# zigbee.net
KiCad netlist of a schematic drawn in Altium Designer
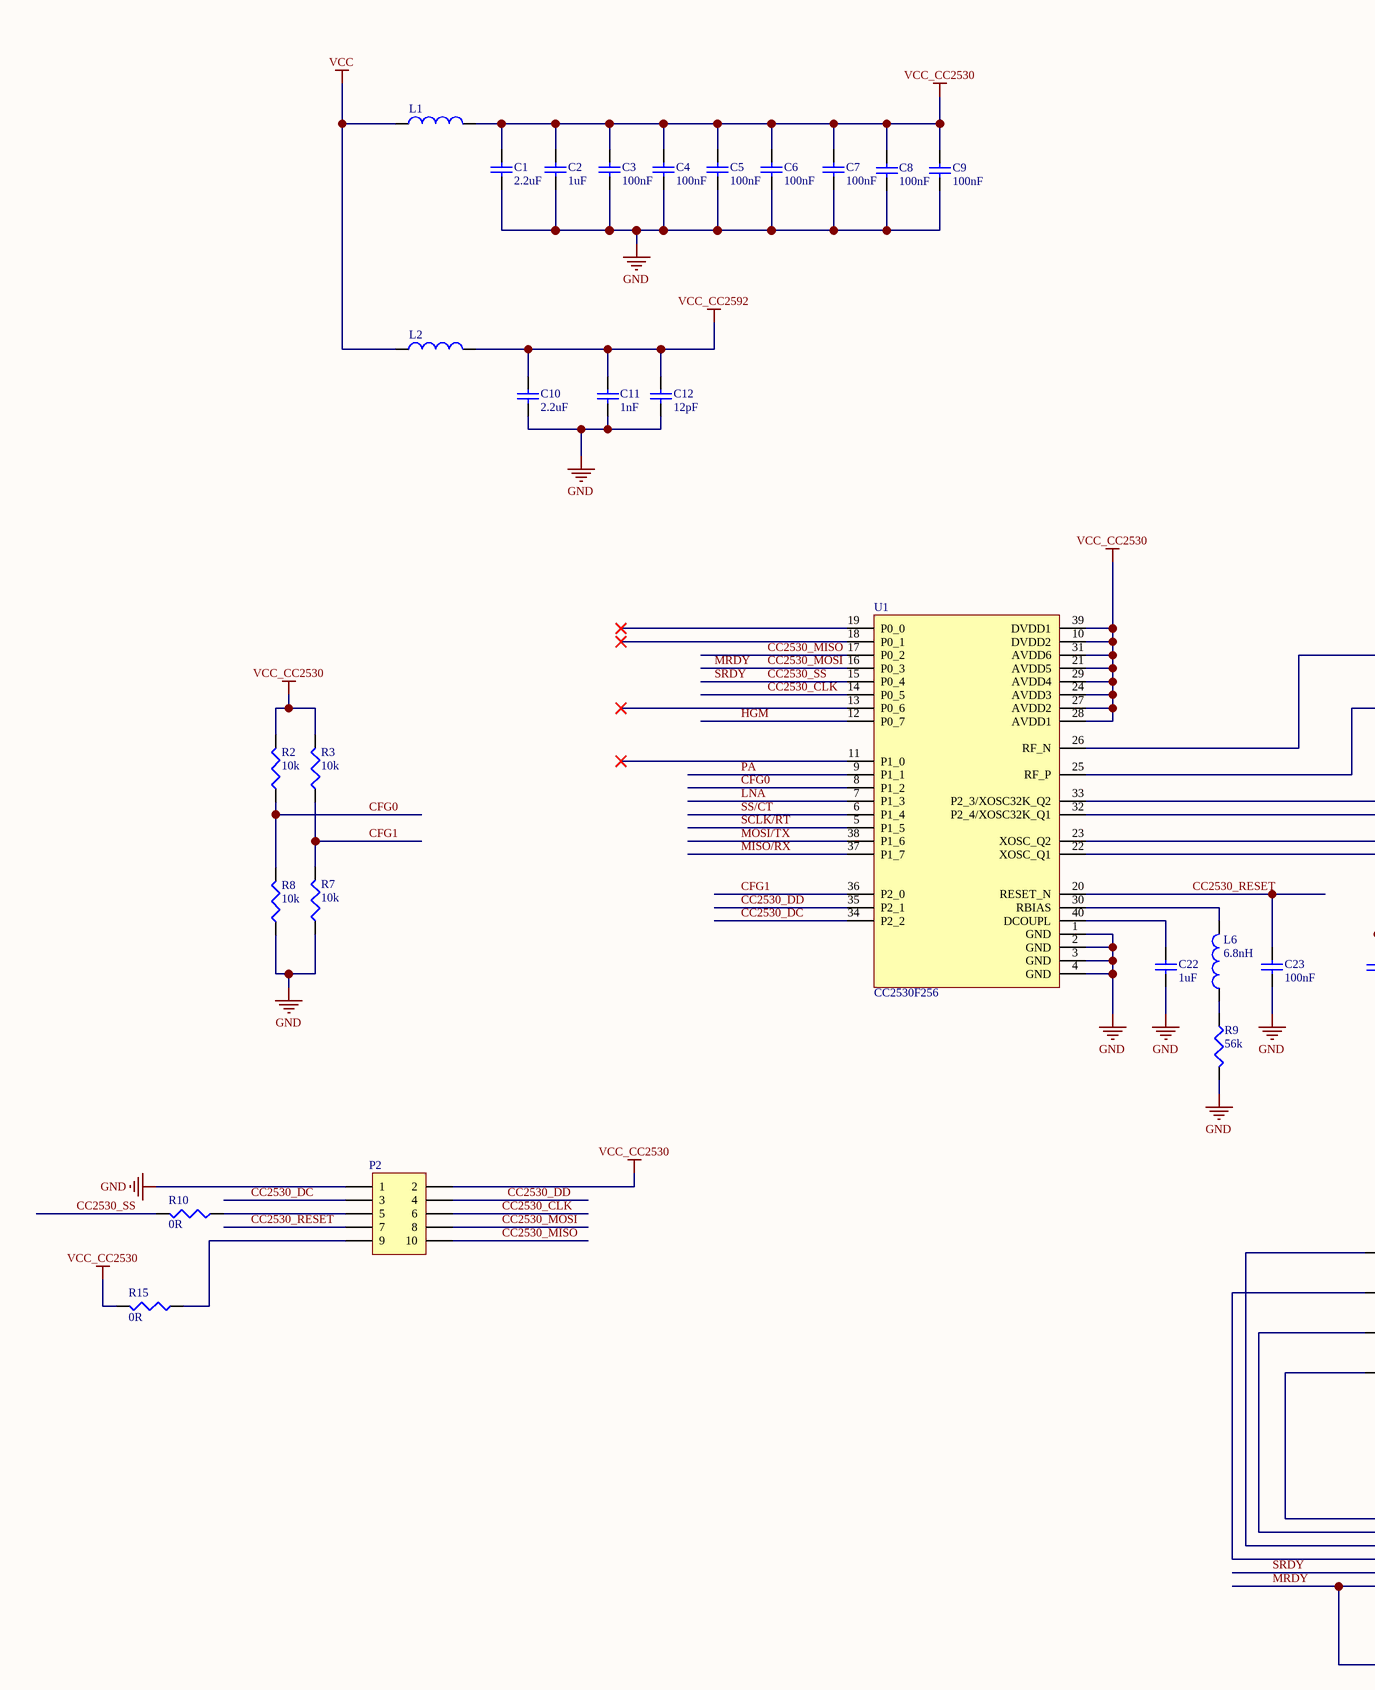
[diagram p0: zigbee.SchDoc, left]
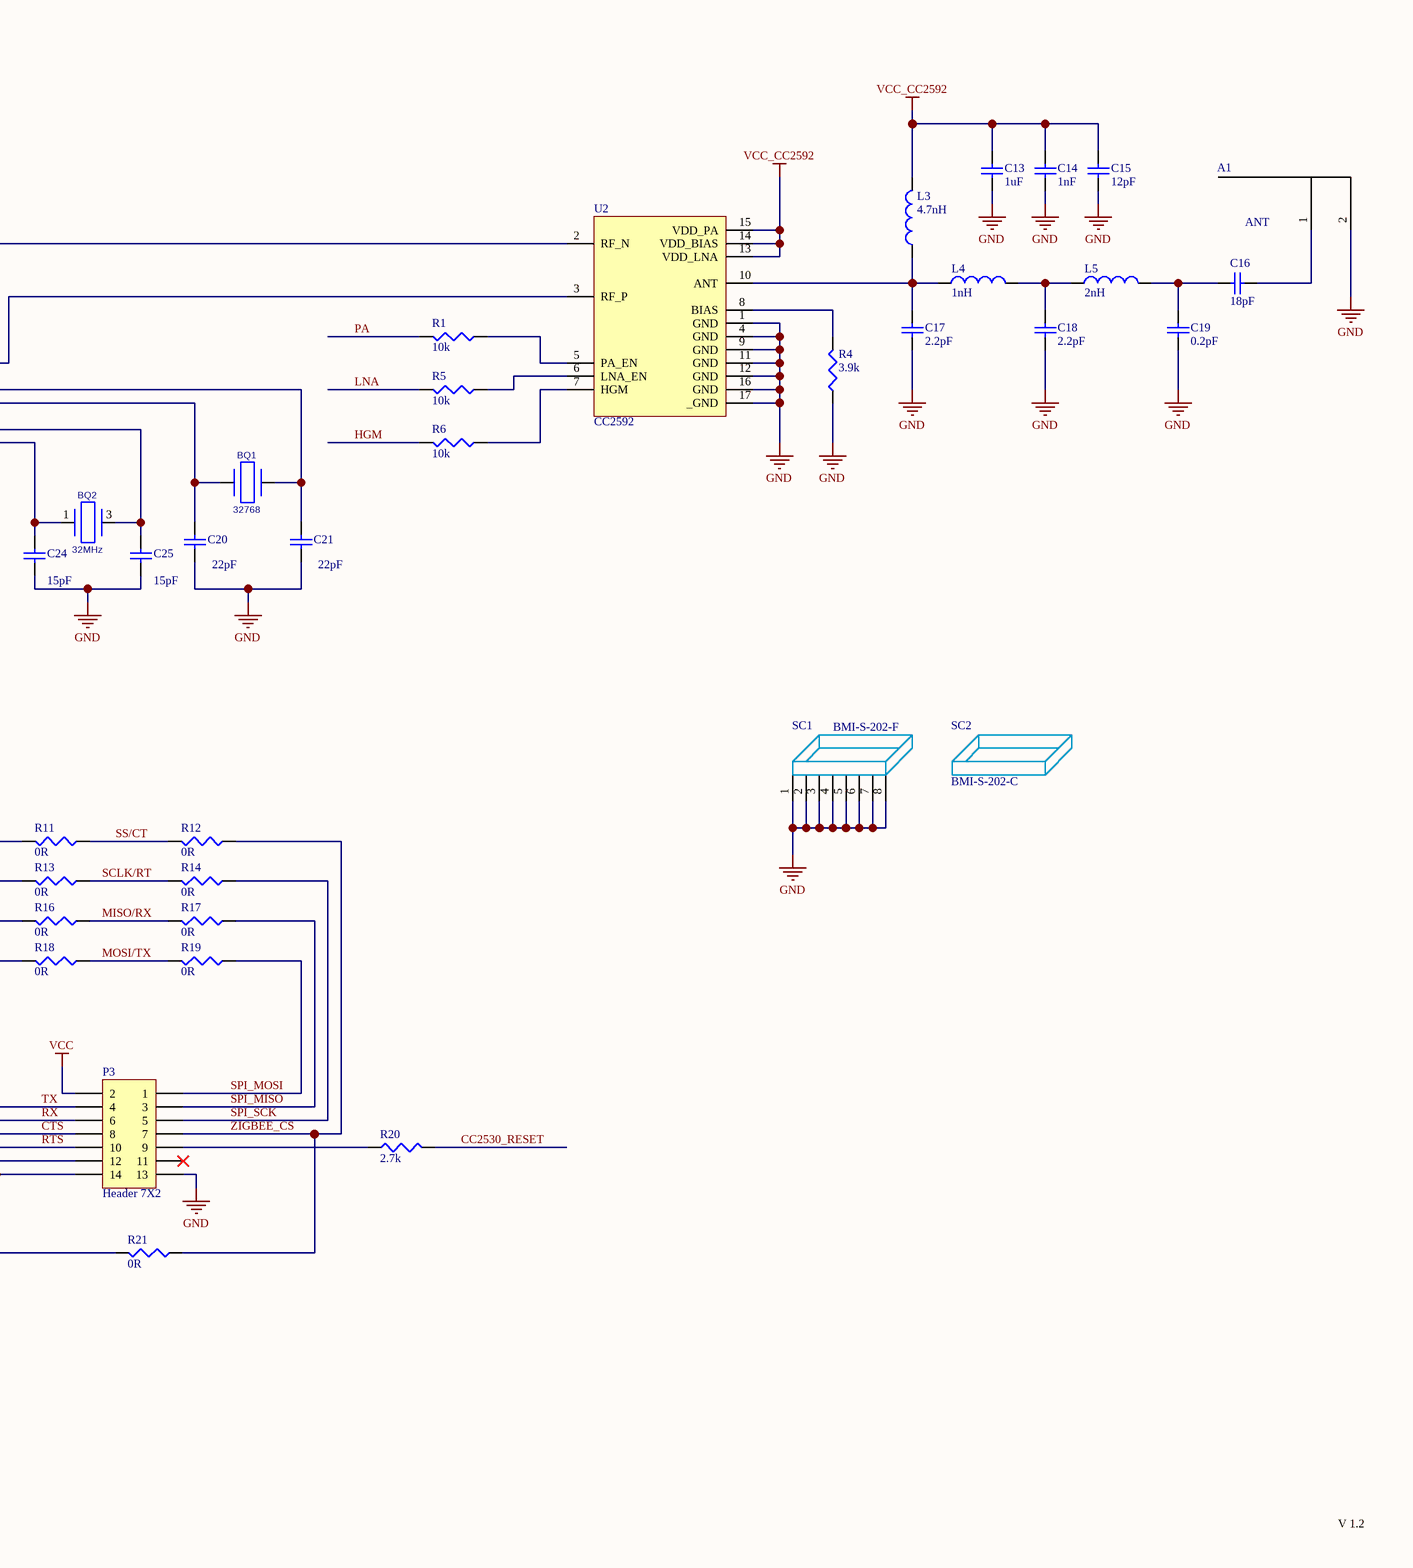
[diagram p1: zigbee.SchDoc, right]

(export (version "E")
  (design (tool "Eeschema 10.0.6"))
  (components
    (comp (ref "A1")
      (value "ANT")
      (footprint "F ant")
      (description "Inverted-F Antenna")
      (fields (field (name "MANUFACTURER PART NUMBER") "PCB ANT"))
      (libsource (lib "CC25xx") (part "ANT"))
    )
    (comp (ref "BQ1")
      (value "32768")
      (footprint "FC-12M")
      (description "CRYSTAL 32.768KHZ 12.5PF SMD")
      (fields
        (field (name "MANUFACTURER PART NUMBER") "FC-12M 32.7680KA-A3")
        (field (name "MANUFACTURER") "EPSON")
      )
      (libsource (lib "*") (part "6LC{colon}308C"))
    )
    (comp (ref "BQ2")
      (value "32MHz")
      (footprint "403C11A32M00000")
      (description "CRYSTAL 32MHZ 10PF SMD")
      (fields
        (field (name "MANUFACTURER PART NUMBER") "403C11A32M00000")
        (field (name "MANUFACTURER") "CTS-Frequency Controls")
      )
      (libsource (lib "*") (part "HC-49SMD"))
    )
    (comp (ref "C1")
      (value "2.2uF")
      (footprint "0402")
      (description "CAP CER 2.2UF 6.3V 20% X5R 0402")
      (fields
        (field (name "MANUFACTURER PART NUMBER") "CL05A225MQ5NNNC")
        (field (name "MANUFACTURER") "Samsung Electro-Mechanics America, Inc")
      )
      (libsource (lib "Miscellaneous Devices") (part "Cap"))
    )
    (comp (ref "C2")
      (value "1uF")
      (footprint "0402")
      (description "CAP CER 1UF 6.3V 10% X5R 0402")
      (fields
        (field (name "MANUFACTURER PART NUMBER") "GRM155R60J105KE19D")
        (field (name "MANUFACTURER") "Murata Electronics North America")
      )
      (libsource (lib "Miscellaneous Devices") (part "Cap"))
    )
    (comp (ref "C3")
      (value "100nF")
      (footprint "0402")
      (description "CAP CER 0.1UF 10V 20% X5R 0402")
      (fields
        (field (name "MANUFACTURER PART NUMBER") "CL05A104MP5NNNC")
        (field (name "MANUFACTURER") "Samsung Electro-Mechanics America, Inc")
      )
      (libsource (lib "Miscellaneous Devices") (part "Cap"))
    )
    (comp (ref "C4")
      (value "100nF")
      (footprint "0402")
      (description "CAP CER 0.1UF 10V 20% X5R 0402")
      (fields
        (field (name "MANUFACTURER PART NUMBER") "CL05A104MP5NNNC")
        (field (name "MANUFACTURER") "Samsung Electro-Mechanics America, Inc")
      )
      (libsource (lib "Miscellaneous Devices") (part "Cap"))
    )
    (comp (ref "C5")
      (value "100nF")
      (footprint "0402")
      (description "CAP CER 0.1UF 10V 20% X5R 0402")
      (fields
        (field (name "MANUFACTURER PART NUMBER") "CL05A104MP5NNNC")
        (field (name "MANUFACTURER") "Samsung Electro-Mechanics America, Inc")
      )
      (libsource (lib "Miscellaneous Devices") (part "Cap"))
    )
    (comp (ref "C6")
      (value "100nF")
      (footprint "0402")
      (description "CAP CER 0.1UF 10V 20% X5R 0402")
      (fields
        (field (name "MANUFACTURER PART NUMBER") "CL05A104MP5NNNC")
        (field (name "MANUFACTURER") "Samsung Electro-Mechanics America, Inc")
      )
      (libsource (lib "Miscellaneous Devices") (part "Cap"))
    )
    (comp (ref "C7")
      (value "100nF")
      (footprint "0402")
      (description "CAP CER 0.1UF 10V 20% X5R 0402")
      (fields
        (field (name "MANUFACTURER PART NUMBER") "CL05A104MP5NNNC")
        (field (name "MANUFACTURER") "Samsung Electro-Mechanics America, Inc")
      )
      (libsource (lib "Miscellaneous Devices") (part "Cap"))
    )
    (comp (ref "C8")
      (value "100nF")
      (footprint "0402")
      (description "CAP CER 0.1UF 10V 20% X5R 0402")
      (fields
        (field (name "MANUFACTURER PART NUMBER") "CL05A104MP5NNNC")
        (field (name "MANUFACTURER") "Samsung Electro-Mechanics America, Inc")
      )
      (libsource (lib "Miscellaneous Devices") (part "Cap"))
    )
    (comp (ref "C9")
      (value "100nF")
      (footprint "0402")
      (description "CAP CER 0.1UF 10V 20% X5R 0402")
      (fields
        (field (name "MANUFACTURER PART NUMBER") "CL05A104MP5NNNC")
        (field (name "MANUFACTURER") "Samsung Electro-Mechanics America, Inc")
      )
      (libsource (lib "Miscellaneous Devices") (part "Cap"))
    )
    (comp (ref "C10")
      (value "2.2uF")
      (footprint "0402")
      (description "CAP CER 2.2UF 6.3V 20% X5R 0402")
      (fields
        (field (name "MANUFACTURER PART NUMBER") "CL05A225MQ5NNNC")
        (field (name "MANUFACTURER") "Samsung Electro-Mechanics America, Inc")
      )
      (libsource (lib "Miscellaneous Devices") (part "Cap"))
    )
    (comp (ref "C11")
      (value "1nF")
      (footprint "0402")
      (description "CAP CER 10000PF 10V 10% X5R 0402")
      (fields
        (field (name "MANUFACTURER PART NUMBER") "GRM155R61A103KA01D")
        (field (name "MANUFACTURER") "Murata Electronics North America")
      )
      (libsource (lib "Miscellaneous Devices") (part "Cap"))
    )
    (comp (ref "C12")
      (value "12pF")
      (footprint "0402")
      (description "CAP CER 12PF 50V 5% NP0 0402")
      (fields
        (field (name "MANUFACTURER PART NUMBER") "GRM1555C1H120JA01D")
        (field (name "MANUFACTURER") "Murata Electronics North America")
      )
      (libsource (lib "Miscellaneous Devices") (part "Cap"))
    )
    (comp (ref "C13")
      (value "1uF")
      (footprint "0402")
      (description "CAP CER 1UF 6.3V 10% X5R 0402")
      (fields
        (field (name "MANUFACTURER PART NUMBER") "GRM155R60J105KE19D")
        (field (name "MANUFACTURER") "Murata Electronics North America")
      )
      (libsource (lib "Miscellaneous Devices") (part "Cap"))
    )
    (comp (ref "C14")
      (value "1nF")
      (footprint "0402")
      (description "CAP CER 10000PF 10V 10% X5R 0402")
      (fields
        (field (name "MANUFACTURER PART NUMBER") "GRM155R61A103KA01D")
        (field (name "MANUFACTURER") "Murata Electronics North America")
      )
      (libsource (lib "Miscellaneous Devices") (part "Cap"))
    )
    (comp (ref "C15")
      (value "12pF")
      (footprint "0402")
      (description "CAP CER 12PF 50V 5% NP0 0402")
      (fields
        (field (name "MANUFACTURER PART NUMBER") "GRM1555C1H120JA01D")
        (field (name "MANUFACTURER") "Murata Electronics North America")
      )
      (libsource (lib "Miscellaneous Devices") (part "Cap"))
    )
    (comp (ref "C16")
      (value "18pF")
      (footprint "0402")
      (description "CAP CER 18PF 50V 5% NP0 0402")
      (fields
        (field (name "MANUFACTURER PART NUMBER") "GRM1555C1H180JA01D")
        (field (name "MANUFACTURER") "Murata Electronics North America")
      )
      (libsource (lib "Miscellaneous Devices") (part "Cap"))
    )
    (comp (ref "C17")
      (value "2.2pF")
      (footprint "0402")
      (description "CAP CER 2.2PF 50V NP0 0402")
      (fields
        (field (name "MANUFACTURER PART NUMBER") "GRM1555C1H2R2BA01D")
        (field (name "MANUFACTURER") "Murata Electronics North America")
      )
      (libsource (lib "Miscellaneous Devices") (part "Cap"))
    )
    (comp (ref "C18")
      (value "2.2pF")
      (footprint "0402")
      (description "CAP CER 2.2PF 50V NP0 0402")
      (fields
        (field (name "MANUFACTURER PART NUMBER") "GRM1555C1H2R2BA01D")
        (field (name "MANUFACTURER") "Murata Electronics North America")
      )
      (libsource (lib "Miscellaneous Devices") (part "Cap"))
    )
    (comp (ref "C19")
      (value "0.2pF")
      (footprint "0402")
      (description "CAP CER 0.2PF 50V NP0 0402")
      (fields
        (field (name "MANUFACTURER PART NUMBER") "GJM1555C1HR20BB01D")
        (field (name "MANUFACTURER") "Murata Electronics North America")
      )
      (libsource (lib "Miscellaneous Devices") (part "Cap"))
    )
    (comp (ref "C20")
      (value "22pF")
      (footprint "0402")
      (description "CAP CER 22PF 50V 5% NP0 0402")
      (fields
        (field (name "MANUFACTURER PART NUMBER") "GRM1555C1H220JA01D")
        (field (name "MANUFACTURER") "Murata Electronics North America")
      )
      (libsource (lib "Miscellaneous Devices") (part "Cap"))
    )
    (comp (ref "C21")
      (value "22pF")
      (footprint "0402")
      (description "CAP CER 22PF 50V 5% NP0 0402")
      (fields
        (field (name "MANUFACTURER PART NUMBER") "GRM1555C1H220JA01D")
        (field (name "MANUFACTURER") "Murata Electronics North America")
      )
      (libsource (lib "Miscellaneous Devices") (part "Cap"))
    )
    (comp (ref "C22")
      (value "1uF")
      (footprint "0402")
      (description "CAP CER 1UF 6.3V 10% X5R 0402")
      (fields
        (field (name "MANUFACTURER PART NUMBER") "GRM155R60J105KE19D")
        (field (name "MANUFACTURER") "Murata Electronics North America")
      )
      (libsource (lib "Miscellaneous Devices") (part "Cap"))
    )
    (comp (ref "C23")
      (value "100nF")
      (footprint "0402")
      (description "CAP CER 0.1UF 10V 20% X5R 0402")
      (fields
        (field (name "MANUFACTURER PART NUMBER") "CL05A104MP5NNNC")
        (field (name "MANUFACTURER") "Samsung Electro-Mechanics America, Inc")
      )
      (libsource (lib "Miscellaneous Devices") (part "Cap"))
    )
    (comp (ref "C24")
      (value "15pF")
      (footprint "0402")
      (description "CAP CER 15PF 50V 5% NP0 0402")
      (fields
        (field (name "MANUFACTURER PART NUMBER") "GRM1555C1H150JA01D")
        (field (name "MANUFACTURER") "Murata Electronics North America")
      )
      (libsource (lib "Miscellaneous Devices") (part "Cap"))
    )
    (comp (ref "C25")
      (value "15pF")
      (footprint "0402")
      (description "CAP CER 15PF 50V 5% NP0 0402")
      (fields
        (field (name "MANUFACTURER PART NUMBER") "GRM1555C1H150JA01D")
        (field (name "MANUFACTURER") "Murata Electronics North America")
      )
      (libsource (lib "Miscellaneous Devices") (part "Cap"))
    )
    (comp (ref "L1")
      (value "Inductor")
      (footprint "0402")
      (description "FILTER CHIP 1000 OHM 250MA 0402")
      (fields
        (field (name "MANUFACTURER PART NUMBER") "BLM15HG102SN1D")
        (field (name "MANUFACTURER") "Murata Electronics North America")
      )
      (libsource (lib "Miscellaneous Devices") (part "Inductor"))
    )
    (comp (ref "L2")
      (value "Inductor")
      (footprint "0603")
      (description "FILTER CHIP 1000 OHM 250MA 0603")
      (fields
        (field (name "MANUFACTURER PART NUMBER") "BLM18HE152SN1D")
        (field (name "MANUFACTURER") "Murata Electronics North America")
      )
      (libsource (lib "Miscellaneous Devices") (part "Inductor"))
    )
    (comp (ref "L3")
      (value "4.7nH")
      (footprint "0402")
      (description "INDUCTOR 4.7NH 300MA 0402")
      (fields
        (field (name "MANUFACTURER PART NUMBER") "LQG15HN4N7S02D")
        (field (name "MANUFACTURER") "Murata Electronics North America")
      )
      (libsource (lib "Miscellaneous Devices") (part "Inductor"))
    )
    (comp (ref "L4")
      (value "1nH")
      (footprint "0402")
      (description "INDUCTOR 1.0NH 300MA 0402")
      (fields
        (field (name "MANUFACTURER PART NUMBER") "LQG15HN1N0S02D")
        (field (name "MANUFACTURER") "Murata Electronics North America")
      )
      (libsource (lib "Miscellaneous Devices") (part "Inductor"))
    )
    (comp (ref "L5")
      (value "2nH")
      (footprint "0402")
      (description "INDUCTOR 2.0NH 300MA 0402")
      (fields
        (field (name "MANUFACTURER PART NUMBER") "LQG15HS2N0S02D")
        (field (name "MANUFACTURER") "Murata Electronics North America")
      )
      (libsource (lib "Miscellaneous Devices") (part "Inductor"))
    )
    (comp (ref "L6")
      (value "6.8nH")
      (footprint "0402")
      (description "INDUCTOR 6.8NH 300MA 0402")
      (fields
        (field (name "MANUFACTURER PART NUMBER") "LQG15HS6N8J02D")
        (field (name "MANUFACTURER") "Murata Electronics North America")
      )
      (libsource (lib "Miscellaneous Devices") (part "Inductor"))
    )
    (comp (ref "P2")
      (value "*")
      (footprint "HDR2X5H")
      (description "CONN HEADER R/A DUAL 10POS GOLD")
      (fields (field (name "MANUFACTURER PART NUMBER") "961210-5604-AR") (field (name "MANUFACTURER") "3M"))
      (libsource (lib "Miscellaneous Connectors") (part "Header 5X2"))
    )
    (comp (ref "P3")
      (value "Header 7X2")
      (footprint "DIP14")
      (description "BERGSTIK II .100\" DR STRAIGHT")
      (fields (field (name "MANUFACTURER PART NUMBER") "67996-114HLF") (field (name "MANUFACTURER") "FCI"))
      (libsource (lib "Miscellaneous Connectors") (part "Header 7X2"))
    )
    (comp (ref "R1")
      (value "10k")
      (footprint "0402")
      (description "RES 10K OHM 1/10W 5% 0402 SMD")
      (fields
        (field (name "MANUFACTURER PART NUMBER") "ERJ-2GEJ103X")
        (field (name "MANUFACTURER") "Panasonic Electronic Components")
      )
      (libsource (lib "Miscellaneous Devices") (part "Res3"))
    )
    (comp (ref "R2")
      (value "10k")
      (footprint "0402")
      (description "RES 10K OHM 1/10W 5% 0402 SMD")
      (fields
        (field (name "MANUFACTURER PART NUMBER") "ERJ-2GEJ103X")
        (field (name "MANUFACTURER") "Panasonic Electronic Components")
      )
      (libsource (lib "Miscellaneous Devices") (part "Res3"))
    )
    (comp (ref "R3")
      (value "10k")
      (footprint "0402")
      (description "RES 10K OHM 1/10W 5% 0402 SMD")
      (fields
        (field (name "MANUFACTURER PART NUMBER") "ERJ-2GEJ103X")
        (field (name "MANUFACTURER") "Panasonic Electronic Components")
      )
      (libsource (lib "Miscellaneous Devices") (part "Res3"))
    )
    (comp (ref "R4")
      (value "3.9k")
      (footprint "0402")
      (description "RES 3.9K OHM 1/10W 1% 0402 SMD")
      (fields
        (field (name "MANUFACTURER PART NUMBER") "ERJ-2RKF3901X")
        (field (name "MANUFACTURER") "Panasonic Electronic Components")
      )
      (libsource (lib "Miscellaneous Devices") (part "Res3"))
    )
    (comp (ref "R5")
      (value "10k")
      (footprint "0402")
      (description "RES 10K OHM 1/10W 5% 0402 SMD")
      (fields
        (field (name "MANUFACTURER PART NUMBER") "ERJ-2GEJ103X")
        (field (name "MANUFACTURER") "Panasonic Electronic Components")
      )
      (libsource (lib "Miscellaneous Devices") (part "Res3"))
    )
    (comp (ref "R6")
      (value "10k")
      (footprint "0402")
      (description "RES 10K OHM 1/10W 5% 0402 SMD")
      (fields
        (field (name "MANUFACTURER PART NUMBER") "ERJ-2GEJ103X")
        (field (name "MANUFACTURER") "Panasonic Electronic Components")
      )
      (libsource (lib "Miscellaneous Devices") (part "Res3"))
    )
    (comp (ref "R7")
      (value "10k")
      (footprint "0402")
      (description "RES 10K OHM 1/10W 5% 0402 SMD")
      (fields
        (field (name "MANUFACTURER PART NUMBER") "ERJ-2GEJ103X")
        (field (name "MANUFACTURER") "Panasonic Electronic Components")
      )
      (libsource (lib "Miscellaneous Devices") (part "Res3"))
    )
    (comp (ref "R8")
      (value "10k")
      (footprint "0402")
      (description "RES 10K OHM 1/10W 5% 0402 SMD")
      (fields
        (field (name "MANUFACTURER PART NUMBER") "ERJ-2GEJ103X")
        (field (name "MANUFACTURER") "Panasonic Electronic Components")
      )
      (libsource (lib "Miscellaneous Devices") (part "Res3"))
    )
    (comp (ref "R9")
      (value "56k")
      (footprint "0402")
      (description "RES 56K OHM 1/10W 1% 0402 SMD")
      (fields
        (field (name "MANUFACTURER PART NUMBER") "ERJ-2RKF5602X")
        (field (name "MANUFACTURER") "Panasonic Electronic Components")
      )
      (libsource (lib "Miscellaneous Devices") (part "Res3"))
    )
    (comp (ref "R10")
      (value "0R")
      (footprint "0402")
      (description "RES 0.0 OHM 1/10W JUMP 0402 SMD")
      (fields
        (field (name "MANUFACTURER PART NUMBER") "ERJ-2GE0R00X")
        (field (name "MANUFACTURER") "Panasonic Electronic Components")
      )
      (libsource (lib "Miscellaneous Devices") (part "Res3"))
    )
    (comp (ref "R11")
      (value "0R")
      (footprint "0402")
      (description "RES 0.0 OHM 1/10W JUMP 0402 SMD")
      (fields
        (field (name "MANUFACTURER PART NUMBER") "ERJ-2GE0R00X")
        (field (name "MANUFACTURER") "Panasonic Electronic Components")
      )
      (libsource (lib "Miscellaneous Devices") (part "Res3"))
    )
    (comp (ref "R12")
      (value "0R")
      (footprint "0402")
      (description "RES 0.0 OHM 1/10W JUMP 0402 SMD")
      (fields
        (field (name "MANUFACTURER PART NUMBER") "ERJ-2GE0R00X")
        (field (name "MANUFACTURER") "Panasonic Electronic Components")
      )
      (libsource (lib "Miscellaneous Devices") (part "Res3"))
    )
    (comp (ref "R13")
      (value "0R")
      (footprint "0402")
      (description "RES 0.0 OHM 1/10W JUMP 0402 SMD")
      (fields
        (field (name "MANUFACTURER PART NUMBER") "ERJ-2GE0R00X")
        (field (name "MANUFACTURER") "Panasonic Electronic Components")
      )
      (libsource (lib "Miscellaneous Devices") (part "Res3"))
    )
    (comp (ref "R14")
      (value "0R")
      (footprint "0402")
      (description "RES 0.0 OHM 1/10W JUMP 0402 SMD")
      (fields
        (field (name "MANUFACTURER PART NUMBER") "ERJ-2GE0R00X")
        (field (name "MANUFACTURER") "Panasonic Electronic Components")
      )
      (libsource (lib "Miscellaneous Devices") (part "Res3"))
    )
    (comp (ref "R15")
      (value "0R")
      (footprint "0402")
      (description "RES 0.0 OHM 1/10W JUMP 0402 SMD")
      (fields
        (field (name "MANUFACTURER PART NUMBER") "ERJ-2GE0R00X")
        (field (name "MANUFACTURER") "Panasonic Electronic Components")
      )
      (libsource (lib "Miscellaneous Devices") (part "Res3"))
    )
    (comp (ref "R16")
      (value "0R")
      (footprint "0402")
      (description "RES 0.0 OHM 1/10W JUMP 0402 SMD")
      (fields
        (field (name "MANUFACTURER PART NUMBER") "ERJ-2GE0R00X")
        (field (name "MANUFACTURER") "Panasonic Electronic Components")
      )
      (libsource (lib "Miscellaneous Devices") (part "Res3"))
    )
    (comp (ref "R17")
      (value "0R")
      (footprint "0402")
      (description "RES 0.0 OHM 1/10W JUMP 0402 SMD")
      (fields
        (field (name "MANUFACTURER PART NUMBER") "ERJ-2GE0R00X")
        (field (name "MANUFACTURER") "Panasonic Electronic Components")
      )
      (libsource (lib "Miscellaneous Devices") (part "Res3"))
    )
    (comp (ref "R18")
      (value "0R")
      (footprint "0402")
      (description "RES 0.0 OHM 1/10W JUMP 0402 SMD")
      (fields
        (field (name "MANUFACTURER PART NUMBER") "ERJ-2GE0R00X")
        (field (name "MANUFACTURER") "Panasonic Electronic Components")
      )
      (libsource (lib "Miscellaneous Devices") (part "Res3"))
    )
    (comp (ref "R19")
      (value "0R")
      (footprint "0402")
      (description "RES 0.0 OHM 1/10W JUMP 0402 SMD")
      (fields
        (field (name "MANUFACTURER PART NUMBER") "ERJ-2GE0R00X")
        (field (name "MANUFACTURER") "Panasonic Electronic Components")
      )
      (libsource (lib "Miscellaneous Devices") (part "Res3"))
    )
    (comp (ref "R20")
      (value "2.7k")
      (footprint "0402")
      (description "RES 2.7K OHM 1/10W 5% 0402 SMD")
      (fields
        (field (name "MANUFACTURER PART NUMBER") "ERJ-2GEJ272X")
        (field (name "MANUFACTURER") "Panasonic Electronic Components")
      )
      (libsource (lib "Miscellaneous Devices") (part "Res3"))
    )
    (comp (ref "R21")
      (value "0R")
      (footprint "0402")
      (description "RES 0.0 OHM 1/10W JUMP 0402 SMD")
      (fields
        (field (name "MANUFACTURER PART NUMBER") "ERJ-2GE0R00X")
        (field (name "MANUFACTURER") "Panasonic Electronic Components")
      )
      (libsource (lib "Miscellaneous Devices") (part "Res3"))
    )
    (comp (ref "SC1")
      (value "BMI-S-202-F")
      (footprint "BMIS_202_F")
      (description "BOARD SHIELD .65X.65\" FRAME")
      (fields (field (name "MANUFACTURER") "Laird Technologies EMI"))
      (libsource (lib "CC25xx") (part "BMI-S-202-F"))
    )
    (comp (ref "SC2")
      (value "BMI-S-202-C")
      (description "BOARD SHIELD .65X.65\" COVER")
      (fields (field (name "MANUFACTURER") "Laird Technologies EMI"))
      (libsource (lib "CC25xx") (part "BMI-S-202-C"))
    )
    (comp (ref "U1")
      (value "CC2530F256")
      (footprint "QFN40")
      (description "IC SOC IEEE 802.15.4/ZIG 40VQFN")
      (fields
        (field (name "MANUFACTURER PART NUMBER") "CC2530F256RHAT")
        (field (name "MANUFACTURER") "Texas Instruments")
      )
      (libsource (lib "CC25xx") (part "CC2530F256"))
    )
    (comp (ref "U2")
      (value "CC2592")
      (footprint "QFN16")
      (description "IC RF FRONT END 2.4GHZ 16-VQFN")
      (fields
        (field (name "MANUFACTURER PART NUMBER") "CC2592RGVT")
        (field (name "MANUFACTURER") "Texas Instruments")
      )
      (libsource (lib "CC25xx") (part "CC2592"))
    )
  )
  (nets
    (net (code "1") (name "/CC2530_CLK") (class "Default")
      (node (ref "P2") (pin "6") (pinfunction "6_6") (pintype "passive"))
      (node (ref "U1") (pin "14") (pinfunction "P0_5_14") (pintype "passive"))
    )
    (net (code "2") (name "/CC2530_DC") (class "Default")
      (node (ref "P2") (pin "3") (pinfunction "3_3") (pintype "passive"))
      (node (ref "U1") (pin "34") (pinfunction "P2_2_34") (pintype "passive"))
    )
    (net (code "3") (name "/CC2530_DD") (class "Default")
      (node (ref "P2") (pin "4") (pinfunction "4_4") (pintype "passive"))
      (node (ref "U1") (pin "35") (pinfunction "P2_1_35") (pintype "passive"))
    )
    (net (code "4") (name "/CC2530_MISO") (class "Default")
      (node (ref "P2") (pin "10") (pinfunction "10_10") (pintype "passive"))
      (node (ref "U1") (pin "17") (pinfunction "P0_2_17") (pintype "passive"))
    )
    (net (code "5") (name "/CC2530_MOSI") (class "Default")
      (node (ref "P2") (pin "8") (pinfunction "8_8") (pintype "passive"))
      (node (ref "P3") (pin "14") (pinfunction "14_14") (pintype "passive"))
      (node (ref "R21") (pin "2") (pinfunction "2_2") (pintype "passive"))
      (node (ref "U1") (pin "16") (pinfunction "P0_3_16") (pintype "passive"))
    )
    (net (code "6") (name "/CC2530_RESET") (class "Default")
      (node (ref "C23") (pin "1") (pinfunction "1_1") (pintype "passive"))
      (node (ref "P2") (pin "7") (pinfunction "7_7") (pintype "passive"))
      (node (ref "R20") (pin "1") (pinfunction "1_1") (pintype "passive"))
      (node (ref "U1") (pin "20") (pinfunction "RESET_N_20") (pintype "passive"))
    )
    (net (code "7") (name "/CC2530_SS") (class "Default")
      (node (ref "P3") (pin "12") (pinfunction "12_12") (pintype "passive"))
      (node (ref "R10") (pin "2") (pinfunction "2_2") (pintype "passive"))
      (node (ref "U1") (pin "15") (pinfunction "P0_4_15") (pintype "passive"))
    )
    (net (code "8") (name "/CFG0") (class "Default")
      (node (ref "R2") (pin "2") (pinfunction "2_2") (pintype "passive"))
      (node (ref "R8") (pin "1") (pinfunction "1_1") (pintype "passive"))
      (node (ref "U1") (pin "8") (pinfunction "P1_2_8") (pintype "passive"))
    )
    (net (code "9") (name "/CFG1") (class "Default")
      (node (ref "R3") (pin "2") (pinfunction "2_2") (pintype "passive"))
      (node (ref "R7") (pin "1") (pinfunction "1_1") (pintype "passive"))
      (node (ref "U1") (pin "36") (pinfunction "P2_0_36") (pintype "passive"))
    )
    (net (code "10") (name "/CTS") (class "Default")
      (node (ref "P3") (pin "8") (pinfunction "8_8") (pintype "passive"))
      (node (ref "R11") (pin "2") (pinfunction "2_2") (pintype "passive"))
    )
    (net (code "11") (name "/HGM") (class "Default")
      (node (ref "R6") (pin "1") (pinfunction "1_1") (pintype "passive"))
      (node (ref "U1") (pin "12") (pinfunction "P0_7_12") (pintype "passive"))
    )
    (net (code "12") (name "/LNA") (class "Default")
      (node (ref "R5") (pin "1") (pinfunction "1_1") (pintype "passive"))
      (node (ref "U1") (pin "7") (pinfunction "P1_3_7") (pintype "passive"))
    )
    (net (code "13") (name "/MISO{slash}RX") (class "Default")
      (node (ref "R16") (pin "1") (pinfunction "1_1") (pintype "passive"))
      (node (ref "R17") (pin "2") (pinfunction "2_2") (pintype "passive"))
      (node (ref "U1") (pin "37") (pinfunction "P1_7_37") (pintype "passive"))
    )
    (net (code "14") (name "/MOSI{slash}TX") (class "Default")
      (node (ref "R18") (pin "1") (pinfunction "1_1") (pintype "passive"))
      (node (ref "R19") (pin "2") (pinfunction "2_2") (pintype "passive"))
      (node (ref "U1") (pin "38") (pinfunction "P1_6_38") (pintype "passive"))
    )
    (net (code "15") (name "/PA") (class "Default")
      (node (ref "R1") (pin "1") (pinfunction "1_1") (pintype "passive"))
      (node (ref "U1") (pin "9") (pinfunction "P1_1_9") (pintype "passive"))
    )
    (net (code "16") (name "/RTS") (class "Default")
      (node (ref "P3") (pin "10") (pinfunction "10_10") (pintype "passive"))
      (node (ref "R13") (pin "2") (pinfunction "2_2") (pintype "passive"))
    )
    (net (code "17") (name "/RX") (class "Default")
      (node (ref "P3") (pin "6") (pinfunction "6_6") (pintype "passive"))
      (node (ref "R16") (pin "2") (pinfunction "2_2") (pintype "passive"))
    )
    (net (code "18") (name "/SCLK{slash}RT") (class "Default")
      (node (ref "R13") (pin "1") (pinfunction "1_1") (pintype "passive"))
      (node (ref "R14") (pin "2") (pinfunction "2_2") (pintype "passive"))
      (node (ref "U1") (pin "5") (pinfunction "P1_5_5") (pintype "passive"))
    )
    (net (code "19") (name "/SPI_MISO") (class "Default")
      (node (ref "P3") (pin "3") (pinfunction "3_3") (pintype "passive"))
      (node (ref "R17") (pin "1") (pinfunction "1_1") (pintype "passive"))
    )
    (net (code "20") (name "/SPI_MOSI") (class "Default")
      (node (ref "P3") (pin "1") (pinfunction "1_1") (pintype "passive"))
      (node (ref "R19") (pin "1") (pinfunction "1_1") (pintype "passive"))
    )
    (net (code "21") (name "/SPI_SCK") (class "Default")
      (node (ref "P3") (pin "5") (pinfunction "5_5") (pintype "passive"))
      (node (ref "R14") (pin "1") (pinfunction "1_1") (pintype "passive"))
    )
    (net (code "22") (name "/SS{slash}CT") (class "Default")
      (node (ref "R11") (pin "1") (pinfunction "1_1") (pintype "passive"))
      (node (ref "R12") (pin "2") (pinfunction "2_2") (pintype "passive"))
      (node (ref "U1") (pin "6") (pinfunction "P1_4_6") (pintype "passive"))
    )
    (net (code "23") (name "/TX") (class "Default")
      (node (ref "P3") (pin "4") (pinfunction "4_4") (pintype "passive"))
      (node (ref "R18") (pin "2") (pinfunction "2_2") (pintype "passive"))
    )
    (net (code "24") (name "/ZIGBEE_CS") (class "Default")
      (node (ref "P3") (pin "7") (pinfunction "7_7") (pintype "passive"))
      (node (ref "R12") (pin "1") (pinfunction "1_1") (pintype "passive"))
      (node (ref "R21") (pin "1") (pinfunction "1_1") (pintype "passive"))
    )
    (net (code "25") (name "GND") (class "Default")
      (node (ref "A1") (pin "2") (pinfunction "2_2") (pintype "passive"))
      (node (ref "C1") (pin "2") (pinfunction "2_2") (pintype "passive"))
      (node (ref "C10") (pin "2") (pinfunction "2_2") (pintype "passive"))
      (node (ref "C11") (pin "1") (pinfunction "1_1") (pintype "passive"))
      (node (ref "C12") (pin "1") (pinfunction "1_1") (pintype "passive"))
      (node (ref "C13") (pin "1") (pinfunction "1_1") (pintype "passive"))
      (node (ref "C14") (pin "1") (pinfunction "1_1") (pintype "passive"))
      (node (ref "C15") (pin "1") (pinfunction "1_1") (pintype "passive"))
      (node (ref "C17") (pin "1") (pinfunction "1_1") (pintype "passive"))
      (node (ref "C18") (pin "1") (pinfunction "1_1") (pintype "passive"))
      (node (ref "C19") (pin "1") (pinfunction "1_1") (pintype "passive"))
      (node (ref "C2") (pin "2") (pinfunction "2_2") (pintype "passive"))
      (node (ref "C20") (pin "1") (pinfunction "1_1") (pintype "passive"))
      (node (ref "C21") (pin "1") (pinfunction "1_1") (pintype "passive"))
      (node (ref "C22") (pin "2") (pinfunction "2_2") (pintype "passive"))
      (node (ref "C23") (pin "2") (pinfunction "2_2") (pintype "passive"))
      (node (ref "C24") (pin "1") (pinfunction "1_1") (pintype "passive"))
      (node (ref "C25") (pin "1") (pinfunction "1_1") (pintype "passive"))
      (node (ref "C3") (pin "2") (pinfunction "2_2") (pintype "passive"))
      (node (ref "C4") (pin "2") (pinfunction "2_2") (pintype "passive"))
      (node (ref "C5") (pin "2") (pinfunction "2_2") (pintype "passive"))
      (node (ref "C6") (pin "2") (pinfunction "2_2") (pintype "passive"))
      (node (ref "C7") (pin "2") (pinfunction "2_2") (pintype "passive"))
      (node (ref "C8") (pin "2") (pinfunction "2_2") (pintype "passive"))
      (node (ref "C9") (pin "2") (pinfunction "2_2") (pintype "passive"))
      (node (ref "P2") (pin "1") (pinfunction "1_1") (pintype "passive"))
      (node (ref "P3") (pin "13") (pinfunction "13_13") (pintype "passive"))
      (node (ref "R4") (pin "1") (pinfunction "1_1") (pintype "passive"))
      (node (ref "R7") (pin "2") (pinfunction "2_2") (pintype "passive"))
      (node (ref "R8") (pin "2") (pinfunction "2_2") (pintype "passive"))
      (node (ref "R9") (pin "2") (pinfunction "2_2") (pintype "passive"))
      (node (ref "SC1") (pin "1") (pinfunction "1_1") (pintype "passive"))
      (node (ref "SC1") (pin "2") (pinfunction "2_2") (pintype "passive"))
      (node (ref "SC1") (pin "3") (pinfunction "3_3") (pintype "passive"))
      (node (ref "SC1") (pin "4") (pinfunction "4_4") (pintype "passive"))
      (node (ref "SC1") (pin "5") (pinfunction "5_5") (pintype "passive"))
      (node (ref "SC1") (pin "6") (pinfunction "6_6") (pintype "passive"))
      (node (ref "SC1") (pin "7") (pinfunction "7_7") (pintype "passive"))
      (node (ref "SC1") (pin "8") (pinfunction "8_8") (pintype "passive"))
      (node (ref "U1") (pin "1") (pinfunction "GND_1") (pintype "passive"))
      (node (ref "U1") (pin "2") (pinfunction "GND_2") (pintype "passive"))
      (node (ref "U1") (pin "3") (pinfunction "GND_3") (pintype "passive"))
      (node (ref "U1") (pin "4") (pinfunction "GND_4") (pintype "passive"))
      (node (ref "U2") (pin "1") (pinfunction "GND_1") (pintype "passive"))
      (node (ref "U2") (pin "11") (pinfunction "GND_11") (pintype "passive"))
      (node (ref "U2") (pin "12") (pinfunction "GND_12") (pintype "passive"))
      (node (ref "U2") (pin "16") (pinfunction "GND_16") (pintype "passive"))
      (node (ref "U2") (pin "17") (pinfunction "_GND_17") (pintype "passive"))
      (node (ref "U2") (pin "4") (pinfunction "GND_4") (pintype "passive"))
      (node (ref "U2") (pin "9") (pinfunction "GND_9") (pintype "passive"))
    )
    (net (code "26") (name "Net-(A1-Pad1)") (class "Default")
      (node (ref "A1") (pin "1") (pinfunction "1_1") (pintype "passive"))
      (node (ref "C16") (pin "2") (pinfunction "2_2") (pintype "passive"))
    )
    (net (code "27") (name "Net-(C16-Pad1)") (class "Default")
      (node (ref "C16") (pin "1") (pinfunction "1_1") (pintype "passive"))
      (node (ref "C19") (pin "2") (pinfunction "2_2") (pintype "passive"))
      (node (ref "L5") (pin "2") (pinfunction "2_2") (pintype "passive"))
    )
    (net (code "28") (name "Net-(C18-Pad2)") (class "Default")
      (node (ref "C18") (pin "2") (pinfunction "2_2") (pintype "passive"))
      (node (ref "L4") (pin "2") (pinfunction "2_2") (pintype "passive"))
      (node (ref "L5") (pin "1") (pinfunction "1_1") (pintype "passive"))
    )
    (net (code "29") (name "Net-(L6-Pad1)") (class "Default")
      (node (ref "L6") (pin "1") (pinfunction "1_1") (pintype "passive"))
      (node (ref "R9") (pin "1") (pinfunction "1_1") (pintype "passive"))
    )
    (net (code "30") (name "Net-(P2-Pad5)") (class "Default")
      (node (ref "P2") (pin "5") (pinfunction "5_5") (pintype "passive"))
      (node (ref "R10") (pin "1") (pinfunction "1_1") (pintype "passive"))
    )
    (net (code "31") (name "Net-(P2-Pad9)") (class "Default")
      (node (ref "P2") (pin "9") (pinfunction "9_9") (pintype "passive"))
      (node (ref "R15") (pin "1") (pinfunction "1_1") (pintype "passive"))
    )
    (net (code "32") (name "Net-(P3-Pad9)") (class "Default")
      (node (ref "P3") (pin "9") (pinfunction "9_9") (pintype "passive"))
      (node (ref "R20") (pin "2") (pinfunction "2_2") (pintype "passive"))
    )
    (net (code "33") (name "Net-(U1-DCOUPL)") (class "Default")
      (node (ref "C22") (pin "1") (pinfunction "1_1") (pintype "passive"))
      (node (ref "U1") (pin "40") (pinfunction "DCOUPL_40") (pintype "passive"))
    )
    (net (code "34") (name "Net-(U1-P2_3{slash}XOSC32K_Q2)") (class "Default")
      (node (ref "BQ1") (pin "2") (pintype "passive"))
      (node (ref "C21") (pin "2") (pinfunction "2_2") (pintype "passive"))
      (node (ref "U1") (pin "33") (pinfunction "P2_3/XOSC32K_Q2_33") (pintype "passive"))
    )
    (net (code "35") (name "Net-(U1-P2_4{slash}XOSC32K_Q1)") (class "Default")
      (node (ref "BQ1") (pin "1") (pintype "passive"))
      (node (ref "C20") (pin "2") (pinfunction "2_2") (pintype "passive"))
      (node (ref "U1") (pin "32") (pinfunction "P2_4/XOSC32K_Q1_32") (pintype "passive"))
    )
    (net (code "36") (name "Net-(U1-RBIAS)") (class "Default")
      (node (ref "L6") (pin "2") (pinfunction "2_2") (pintype "passive"))
      (node (ref "U1") (pin "30") (pinfunction "RBIAS_30") (pintype "passive"))
    )
    (net (code "37") (name "Net-(U1-RF_N)") (class "Default")
      (node (ref "U1") (pin "26") (pinfunction "RF_N_26") (pintype "passive"))
      (node (ref "U2") (pin "2") (pinfunction "RF_N_2") (pintype "passive"))
    )
    (net (code "38") (name "Net-(U1-RF_P)") (class "Default")
      (node (ref "U1") (pin "25") (pinfunction "RF_P_25") (pintype "passive"))
      (node (ref "U2") (pin "3") (pinfunction "RF_P_3") (pintype "passive"))
    )
    (net (code "39") (name "Net-(U1-XOSC_Q1)") (class "Default")
      (node (ref "BQ2") (pin "1") (pintype "passive"))
      (node (ref "C24") (pin "2") (pinfunction "2_2") (pintype "passive"))
      (node (ref "U1") (pin "22") (pinfunction "XOSC_Q1_22") (pintype "passive"))
    )
    (net (code "40") (name "Net-(U1-XOSC_Q2)") (class "Default")
      (node (ref "BQ2") (pin "3") (pintype "passive"))
      (node (ref "C25") (pin "2") (pinfunction "2_2") (pintype "passive"))
      (node (ref "U1") (pin "23") (pinfunction "XOSC_Q2_23") (pintype "passive"))
    )
    (net (code "41") (name "Net-(U2-ANT)") (class "Default")
      (node (ref "C17") (pin "2") (pinfunction "2_2") (pintype "passive"))
      (node (ref "L3") (pin "1") (pinfunction "1_1") (pintype "passive"))
      (node (ref "L4") (pin "1") (pinfunction "1_1") (pintype "passive"))
      (node (ref "U2") (pin "10") (pinfunction "ANT_10") (pintype "passive"))
    )
    (net (code "42") (name "Net-(U2-BIAS)") (class "Default")
      (node (ref "R4") (pin "2") (pinfunction "2_2") (pintype "passive"))
      (node (ref "U2") (pin "8") (pinfunction "BIAS_8") (pintype "passive"))
    )
    (net (code "43") (name "Net-(U2-HGM)") (class "Default")
      (node (ref "R6") (pin "2") (pinfunction "2_2") (pintype "passive"))
      (node (ref "U2") (pin "7") (pinfunction "HGM_7") (pintype "passive"))
    )
    (net (code "44") (name "Net-(U2-LNA_EN)") (class "Default")
      (node (ref "R5") (pin "2") (pinfunction "2_2") (pintype "passive"))
      (node (ref "U2") (pin "6") (pinfunction "LNA_EN_6") (pintype "passive"))
    )
    (net (code "45") (name "Net-(U2-PA_EN)") (class "Default")
      (node (ref "R1") (pin "2") (pinfunction "2_2") (pintype "passive"))
      (node (ref "U2") (pin "5") (pinfunction "PA_EN_5") (pintype "passive"))
    )
    (net (code "46") (name "VCC") (class "Default")
      (node (ref "L1") (pin "1") (pinfunction "1_1") (pintype "passive"))
      (node (ref "L2") (pin "1") (pinfunction "1_1") (pintype "passive"))
      (node (ref "P3") (pin "2") (pinfunction "2_2") (pintype "passive"))
    )
    (net (code "47") (name "VCC_CC2530") (class "Default")
      (node (ref "C1") (pin "1") (pinfunction "1_1") (pintype "passive"))
      (node (ref "C2") (pin "1") (pinfunction "1_1") (pintype "passive"))
      (node (ref "C3") (pin "1") (pinfunction "1_1") (pintype "passive"))
      (node (ref "C4") (pin "1") (pinfunction "1_1") (pintype "passive"))
      (node (ref "C5") (pin "1") (pinfunction "1_1") (pintype "passive"))
      (node (ref "C6") (pin "1") (pinfunction "1_1") (pintype "passive"))
      (node (ref "C7") (pin "1") (pinfunction "1_1") (pintype "passive"))
      (node (ref "C8") (pin "1") (pinfunction "1_1") (pintype "passive"))
      (node (ref "C9") (pin "1") (pinfunction "1_1") (pintype "passive"))
      (node (ref "L1") (pin "2") (pinfunction "2_2") (pintype "passive"))
      (node (ref "P2") (pin "2") (pinfunction "2_2") (pintype "passive"))
      (node (ref "R15") (pin "2") (pinfunction "2_2") (pintype "passive"))
      (node (ref "R2") (pin "1") (pinfunction "1_1") (pintype "passive"))
      (node (ref "R3") (pin "1") (pinfunction "1_1") (pintype "passive"))
      (node (ref "U1") (pin "10") (pinfunction "DVDD2_10") (pintype "passive"))
      (node (ref "U1") (pin "21") (pinfunction "AVDD5_21") (pintype "passive"))
      (node (ref "U1") (pin "24") (pinfunction "AVDD3_24") (pintype "passive"))
      (node (ref "U1") (pin "27") (pinfunction "AVDD2_27") (pintype "passive"))
      (node (ref "U1") (pin "28") (pinfunction "AVDD1_28") (pintype "passive"))
      (node (ref "U1") (pin "29") (pinfunction "AVDD4_29") (pintype "passive"))
      (node (ref "U1") (pin "31") (pinfunction "AVDD6_31") (pintype "passive"))
      (node (ref "U1") (pin "39") (pinfunction "DVDD1_39") (pintype "passive"))
    )
    (net (code "48") (name "VCC_CC2592") (class "Default")
      (node (ref "C10") (pin "1") (pinfunction "1_1") (pintype "passive"))
      (node (ref "C11") (pin "2") (pinfunction "2_2") (pintype "passive"))
      (node (ref "C12") (pin "2") (pinfunction "2_2") (pintype "passive"))
      (node (ref "C13") (pin "2") (pinfunction "2_2") (pintype "passive"))
      (node (ref "C14") (pin "2") (pinfunction "2_2") (pintype "passive"))
      (node (ref "C15") (pin "2") (pinfunction "2_2") (pintype "passive"))
      (node (ref "L2") (pin "2") (pinfunction "2_2") (pintype "passive"))
      (node (ref "L3") (pin "2") (pinfunction "2_2") (pintype "passive"))
      (node (ref "U2") (pin "13") (pinfunction "VDD_LNA_13") (pintype "passive"))
      (node (ref "U2") (pin "14") (pinfunction "VDD_BIAS_14") (pintype "passive"))
      (node (ref "U2") (pin "15") (pinfunction "VDD_PA_15") (pintype "passive"))
    )
    (net (code "49") (name "unconnected-(P3-Pad11)") (class "Default")
      (node (ref "P3") (pin "11") (pinfunction "11_11") (pintype "passive+no_connect"))
    )
    (net (code "50") (name "unconnected-(U1-P0_0-Pad19)") (class "Default")
      (node (ref "U1") (pin "19") (pinfunction "P0_0_19") (pintype "passive+no_connect"))
    )
    (net (code "51") (name "unconnected-(U1-P0_1-Pad18)") (class "Default")
      (node (ref "U1") (pin "18") (pinfunction "P0_1_18") (pintype "passive+no_connect"))
    )
    (net (code "52") (name "unconnected-(U1-P0_6-Pad13)") (class "Default")
      (node (ref "U1") (pin "13") (pinfunction "P0_6_13") (pintype "passive+no_connect"))
    )
    (net (code "53") (name "unconnected-(U1-P1_0-Pad11)") (class "Default")
      (node (ref "U1") (pin "11") (pinfunction "P1_0_11") (pintype "passive+no_connect"))
    )
  )
)
